# ATMega8Motherboard.net
KiCad netlist of a schematic drawn in EAGLE
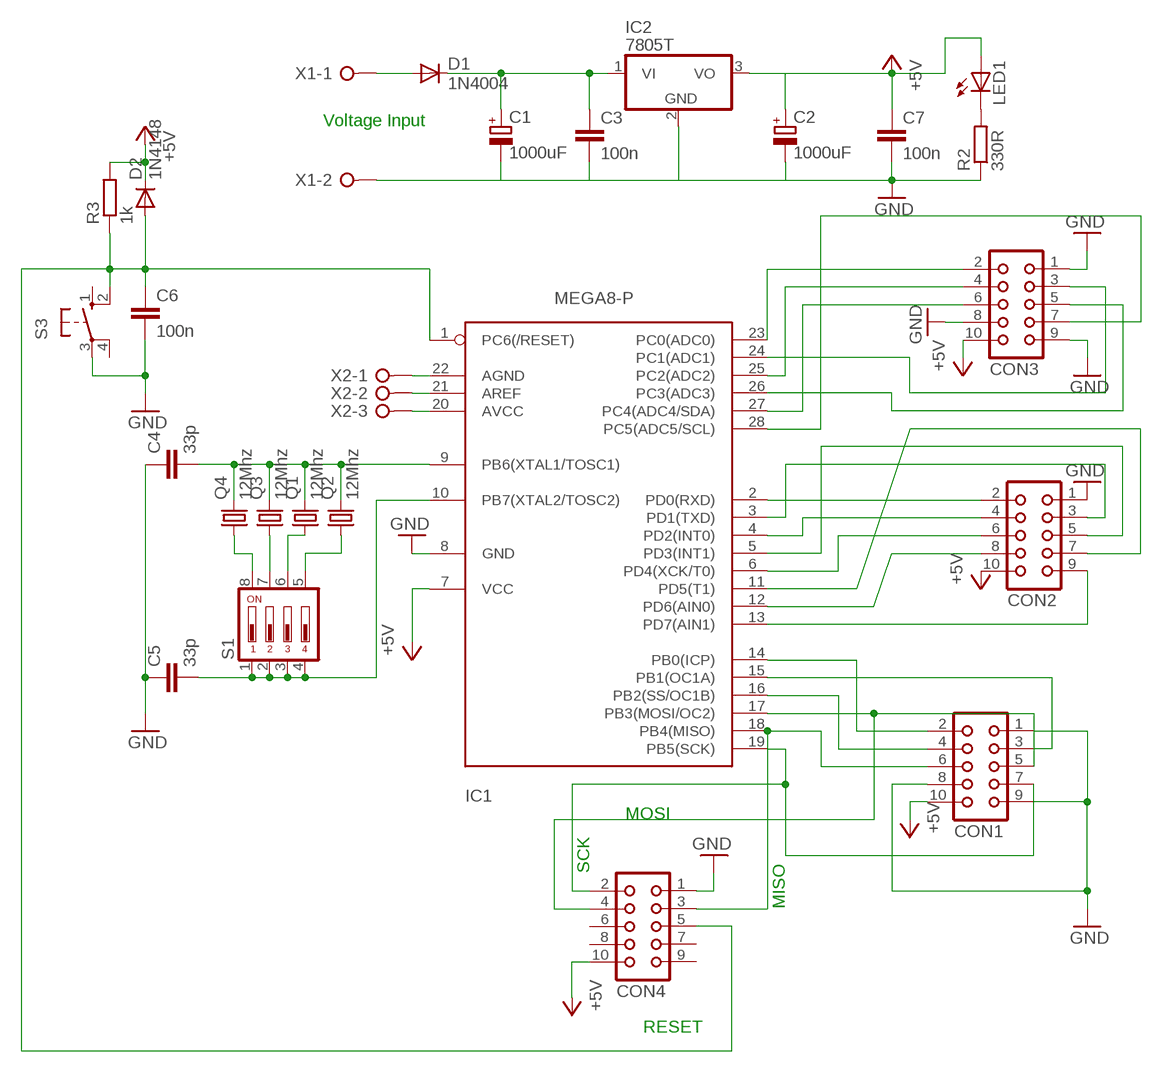
[diagram p0: schematic, sheet 1]

(export (version "E")
  (design (tool "Eeschema 10.0.6"))
  (components
    (comp (ref "C1")
      (value "1000uF")
      (footprint "eagle-import:E2,5-7")
      (libsource (lib "eagle-import") (part "CPOL-EUE2.5-7"))
    )
    (comp (ref "C2")
      (value "1000uF")
      (footprint "eagle-import:E2,5-7")
      (libsource (lib "eagle-import") (part "CPOL-EUE2.5-7"))
    )
    (comp (ref "C3")
      (value "100n")
      (footprint "eagle-import:C025-024X044")
      (libsource (lib "eagle-import") (part "C-EU025-024X044"))
    )
    (comp (ref "C4")
      (value "33p")
      (footprint "eagle-import:C025-024X044")
      (libsource (lib "eagle-import") (part "C-EU025-024X044"))
    )
    (comp (ref "C5")
      (value "33p")
      (footprint "eagle-import:C025-024X044")
      (libsource (lib "eagle-import") (part "C-EU025-024X044"))
    )
    (comp (ref "C6")
      (value "100n")
      (footprint "eagle-import:C025-024X044")
      (libsource (lib "eagle-import") (part "C-EU025-024X044"))
    )
    (comp (ref "C7")
      (value "100n")
      (footprint "eagle-import:C025-024X044")
      (libsource (lib "eagle-import") (part "C-EU025-024X044"))
    )
    (comp (ref "CON1")
      (value "CON10")
      (footprint "eagle-import:CON10")
      (libsource (lib "eagle-import") (part "CON10"))
    )
    (comp (ref "CON2")
      (value "CON10")
      (footprint "eagle-import:CON10")
      (libsource (lib "eagle-import") (part "CON10"))
    )
    (comp (ref "CON3")
      (value "CON10")
      (footprint "eagle-import:CON10")
      (libsource (lib "eagle-import") (part "CON10"))
    )
    (comp (ref "CON4")
      (value "CON10")
      (footprint "eagle-import:CON10")
      (libsource (lib "eagle-import") (part "CON10"))
    )
    (comp (ref "D1")
      (value "1N4004")
      (footprint "eagle-import:DO41-10")
      (libsource (lib "eagle-import") (part "1N4004"))
    )
    (comp (ref "D2")
      (value "1N4148")
      (footprint "eagle-import:DO35-10")
      (libsource (lib "eagle-import") (part "1N4148"))
    )
    (comp (ref "IC1")
      (value "MEGA8-P")
      (footprint "eagle-import:DIL28-3")
      (libsource (lib "eagle-import") (part "MEGA8-P"))
    )
    (comp (ref "IC2")
      (value "7805T")
      (footprint "eagle-import:TO220H")
      (libsource (lib "eagle-import") (part "78T05"))
    )
    (comp (ref "LED1")
      (value "LED5MM")
      (footprint "eagle-import:LED5MM")
      (libsource (lib "eagle-import") (part "LED5MM"))
    )
    (comp (ref "Q1")
      (value "12Mhz")
      (footprint "eagle-import:HC18U-V")
      (libsource (lib "eagle-import") (part "CRYSTALHC18U-V"))
    )
    (comp (ref "Q2")
      (value "12Mhz")
      (footprint "eagle-import:HC18U-V")
      (libsource (lib "eagle-import") (part "CRYSTALHC18U-V"))
    )
    (comp (ref "Q3")
      (value "12Mhz")
      (footprint "eagle-import:HC18U-V")
      (libsource (lib "eagle-import") (part "CRYSTALHC18U-V"))
    )
    (comp (ref "Q4")
      (value "12Mhz")
      (footprint "eagle-import:HC18U-V")
      (libsource (lib "eagle-import") (part "CRYSTALHC18U-V"))
    )
    (comp (ref "R2")
      (value "330R")
      (footprint "eagle-import:0204_5")
      (libsource (lib "eagle-import") (part "R-EU_0204/5"))
    )
    (comp (ref "R3")
      (value "1k")
      (footprint "eagle-import:0204_5")
      (libsource (lib "eagle-import") (part "R-EU_0204/5"))
    )
    (comp (ref "S1")
      (value "DIP04YL")
      (footprint "eagle-import:DIP04YL")
      (libsource (lib "eagle-import") (part "DIP04YL"))
    )
    (comp (ref "S3")
      (value "10-XX")
      (footprint "eagle-import:B3F-10XX")
      (fields (field (name "MPN") "B3F-1000"))
      (libsource (lib "eagle-import") (part "10-XX"))
    )
    (comp (ref "X1")
      (value "W237-02P")
      (footprint "eagle-import:W237-132")
      (libsource (lib "eagle-import") (part "W237-02P"))
    )
    (comp (ref "X2")
      (value "W237-03P")
      (footprint "eagle-import:W237-133")
      (libsource (lib "eagle-import") (part "W237-03P"))
    )
  )
  (nets
    (net (code "1") (name "+5V") (class "Default")
      (node (ref "C2") (pin "+") (pinfunction "+_+") (pintype "passive"))
      (node (ref "C7") (pin "1") (pinfunction "1_1") (pintype "passive"))
      (node (ref "CON1") (pin "10") (pinfunction "10_10") (pintype "passive"))
      (node (ref "CON2") (pin "10") (pinfunction "10_10") (pintype "passive"))
      (node (ref "CON3") (pin "10") (pinfunction "10_10") (pintype "passive"))
      (node (ref "CON4") (pin "10") (pinfunction "10_10") (pintype "passive"))
      (node (ref "D2") (pin "C") (pinfunction "C_C") (pintype "passive"))
      (node (ref "IC1") (pin "7") (pinfunction "VCC_7") (pintype "bidirectional"))
      (node (ref "IC2") (pin "3") (pinfunction "VO_3") (pintype "passive"))
      (node (ref "LED1") (pin "A") (pinfunction "A_A") (pintype "passive"))
      (node (ref "R3") (pin "2") (pinfunction "2_2") (pintype "passive"))
    )
    (net (code "2") (name "GND") (class "Default")
      (node (ref "C1") (pin "-") (pinfunction "-_-") (pintype "passive"))
      (node (ref "C2") (pin "-") (pinfunction "-_-") (pintype "passive"))
      (node (ref "C3") (pin "2") (pinfunction "2_2") (pintype "passive"))
      (node (ref "C4") (pin "1") (pinfunction "1_1") (pintype "passive"))
      (node (ref "C5") (pin "1") (pinfunction "1_1") (pintype "passive"))
      (node (ref "C6") (pin "2") (pinfunction "2_2") (pintype "passive"))
      (node (ref "C7") (pin "2") (pinfunction "2_2") (pintype "passive"))
      (node (ref "CON1") (pin "1") (pinfunction "1_1") (pintype "passive"))
      (node (ref "CON1") (pin "8") (pinfunction "8_8") (pintype "passive"))
      (node (ref "CON1") (pin "9") (pinfunction "9_9") (pintype "passive"))
      (node (ref "CON2") (pin "1") (pinfunction "1_1") (pintype "passive"))
      (node (ref "CON3") (pin "1") (pinfunction "1_1") (pintype "passive"))
      (node (ref "CON3") (pin "8") (pinfunction "8_8") (pintype "passive"))
      (node (ref "CON3") (pin "9") (pinfunction "9_9") (pintype "passive"))
      (node (ref "CON4") (pin "1") (pinfunction "1_1") (pintype "passive"))
      (node (ref "IC1") (pin "8") (pinfunction "GND_8") (pintype "bidirectional"))
      (node (ref "IC2") (pin "2") (pinfunction "GND_2") (pintype "passive"))
      (node (ref "R2") (pin "1") (pinfunction "1_1") (pintype "passive"))
      (node (ref "S3") (pin "3") (pinfunction "P_3") (pintype "passive"))
      (node (ref "X1") (pin "2") (pinfunction "KL_2") (pintype "passive"))
    )
    (net (code "3") (name "Net-(IC1-AGND)") (class "Default")
      (node (ref "IC1") (pin "22") (pinfunction "AGND_22") (pintype "bidirectional"))
      (node (ref "X2") (pin "1") (pinfunction "KL_1") (pintype "passive"))
    )
    (net (code "4") (name "Net-(IC1-AREF)") (class "Default")
      (node (ref "IC1") (pin "21") (pinfunction "AREF_21") (pintype "bidirectional"))
      (node (ref "X2") (pin "2") (pinfunction "KL_2") (pintype "passive"))
    )
    (net (code "5") (name "Net-(IC1-AVCC)") (class "Default")
      (node (ref "IC1") (pin "20") (pinfunction "AVCC_20") (pintype "bidirectional"))
      (node (ref "X2") (pin "3") (pinfunction "KL_3") (pintype "passive"))
    )
    (net (code "6") (name "Net-(IC1-PB0(ICP))") (class "Default")
      (node (ref "CON1") (pin "2") (pinfunction "2_2") (pintype "passive"))
      (node (ref "IC1") (pin "14") (pinfunction "PB0(ICP)_14") (pintype "bidirectional"))
    )
    (net (code "7") (name "Net-(IC1-PB1(OC1A))") (class "Default")
      (node (ref "CON1") (pin "3") (pinfunction "3_3") (pintype "passive"))
      (node (ref "IC1") (pin "15") (pinfunction "PB1(OC1A)_15") (pintype "bidirectional"))
    )
    (net (code "8") (name "Net-(IC1-PB2(SS{slash}OC1B))") (class "Default")
      (node (ref "CON1") (pin "4") (pinfunction "4_4") (pintype "passive"))
      (node (ref "IC1") (pin "16") (pinfunction "PB2(SS/OC1B)_16") (pintype "bidirectional"))
    )
    (net (code "9") (name "Net-(IC1-PB3(MOSI{slash}OC2))") (class "Default")
      (node (ref "CON1") (pin "5") (pinfunction "5_5") (pintype "passive"))
      (node (ref "CON4") (pin "4") (pinfunction "4_4") (pintype "passive"))
      (node (ref "IC1") (pin "17") (pinfunction "PB3(MOSI/OC2)_17") (pintype "bidirectional"))
    )
    (net (code "10") (name "Net-(IC1-PB4(MISO))") (class "Default")
      (node (ref "CON1") (pin "6") (pinfunction "6_6") (pintype "passive"))
      (node (ref "CON4") (pin "3") (pinfunction "3_3") (pintype "passive"))
      (node (ref "IC1") (pin "18") (pinfunction "PB4(MISO)_18") (pintype "bidirectional"))
    )
    (net (code "11") (name "Net-(IC1-PB5(SCK))") (class "Default")
      (node (ref "CON1") (pin "7") (pinfunction "7_7") (pintype "passive"))
      (node (ref "CON4") (pin "2") (pinfunction "2_2") (pintype "passive"))
      (node (ref "IC1") (pin "19") (pinfunction "PB5(SCK)_19") (pintype "bidirectional"))
    )
    (net (code "12") (name "Net-(IC1-PB6(XTAL1{slash}TOSC1))") (class "Default")
      (node (ref "C4") (pin "2") (pinfunction "2_2") (pintype "passive"))
      (node (ref "IC1") (pin "9") (pinfunction "PB6(XTAL1/TOSC1)_9") (pintype "bidirectional"))
      (node (ref "Q1") (pin "2") (pinfunction "2_2") (pintype "passive"))
      (node (ref "Q2") (pin "2") (pinfunction "2_2") (pintype "passive"))
      (node (ref "Q3") (pin "2") (pinfunction "2_2") (pintype "passive"))
      (node (ref "Q4") (pin "2") (pinfunction "2_2") (pintype "passive"))
    )
    (net (code "13") (name "Net-(IC1-PB7(XTAL2{slash}TOSC2))") (class "Default")
      (node (ref "C5") (pin "2") (pinfunction "2_2") (pintype "passive"))
      (node (ref "IC1") (pin "10") (pinfunction "PB7(XTAL2/TOSC2)_10") (pintype "bidirectional"))
      (node (ref "S1") (pin "1") (pinfunction "1_1") (pintype "passive"))
      (node (ref "S1") (pin "2") (pinfunction "2_2") (pintype "passive"))
      (node (ref "S1") (pin "3") (pinfunction "3_3") (pintype "passive"))
      (node (ref "S1") (pin "4") (pinfunction "4_4") (pintype "passive"))
    )
    (net (code "14") (name "Net-(IC1-PC0(ADC0))") (class "Default")
      (node (ref "CON3") (pin "2") (pinfunction "2_2") (pintype "passive"))
      (node (ref "IC1") (pin "23") (pinfunction "PC0(ADC0)_23") (pintype "bidirectional"))
    )
    (net (code "15") (name "Net-(IC1-PC1(ADC1))") (class "Default")
      (node (ref "CON3") (pin "3") (pinfunction "3_3") (pintype "passive"))
      (node (ref "IC1") (pin "24") (pinfunction "PC1(ADC1)_24") (pintype "bidirectional"))
    )
    (net (code "16") (name "Net-(IC1-PC2(ADC2))") (class "Default")
      (node (ref "CON3") (pin "4") (pinfunction "4_4") (pintype "passive"))
      (node (ref "IC1") (pin "25") (pinfunction "PC2(ADC2)_25") (pintype "bidirectional"))
    )
    (net (code "17") (name "Net-(IC1-PC3(ADC3))") (class "Default")
      (node (ref "CON3") (pin "5") (pinfunction "5_5") (pintype "passive"))
      (node (ref "IC1") (pin "26") (pinfunction "PC3(ADC3)_26") (pintype "bidirectional"))
    )
    (net (code "18") (name "Net-(IC1-PC4(ADC4{slash}SDA))") (class "Default")
      (node (ref "CON3") (pin "6") (pinfunction "6_6") (pintype "passive"))
      (node (ref "IC1") (pin "27") (pinfunction "PC4(ADC4/SDA)_27") (pintype "bidirectional"))
    )
    (net (code "19") (name "Net-(IC1-PC5(ADC5{slash}SCL))") (class "Default")
      (node (ref "CON3") (pin "7") (pinfunction "7_7") (pintype "passive"))
      (node (ref "IC1") (pin "28") (pinfunction "PC5(ADC5/SCL)_28") (pintype "bidirectional"))
    )
    (net (code "20") (name "Net-(IC1-PC6({slash}RESET))") (class "Default")
      (node (ref "C6") (pin "1") (pinfunction "1_1") (pintype "passive"))
      (node (ref "CON4") (pin "5") (pinfunction "5_5") (pintype "passive"))
      (node (ref "D2") (pin "A") (pinfunction "A_A") (pintype "passive"))
      (node (ref "IC1") (pin "1") (pinfunction "PC6(/RESET)_1") (pintype "bidirectional"))
      (node (ref "R3") (pin "1") (pinfunction "1_1") (pintype "passive"))
      (node (ref "S3") (pin "2") (pinfunction "S1_2") (pintype "passive"))
    )
    (net (code "21") (name "Net-(IC1-PD0(RXD))") (class "Default")
      (node (ref "CON2") (pin "2") (pinfunction "2_2") (pintype "passive"))
      (node (ref "IC1") (pin "2") (pinfunction "PD0(RXD)_2") (pintype "bidirectional"))
    )
    (net (code "22") (name "Net-(IC1-PD1(TXD))") (class "Default")
      (node (ref "CON2") (pin "3") (pinfunction "3_3") (pintype "passive"))
      (node (ref "IC1") (pin "3") (pinfunction "PD1(TXD)_3") (pintype "bidirectional"))
    )
    (net (code "23") (name "Net-(IC1-PD2(INT0))") (class "Default")
      (node (ref "CON2") (pin "4") (pinfunction "4_4") (pintype "passive"))
      (node (ref "IC1") (pin "4") (pinfunction "PD2(INT0)_4") (pintype "bidirectional"))
    )
    (net (code "24") (name "Net-(IC1-PD3(INT1))") (class "Default")
      (node (ref "CON2") (pin "5") (pinfunction "5_5") (pintype "passive"))
      (node (ref "IC1") (pin "5") (pinfunction "PD3(INT1)_5") (pintype "bidirectional"))
    )
    (net (code "25") (name "Net-(IC1-PD4(XCK{slash}T0))") (class "Default")
      (node (ref "CON2") (pin "6") (pinfunction "6_6") (pintype "passive"))
      (node (ref "IC1") (pin "6") (pinfunction "PD4(XCK/T0)_6") (pintype "bidirectional"))
    )
    (net (code "26") (name "Net-(IC1-PD5(T1))") (class "Default")
      (node (ref "CON2") (pin "7") (pinfunction "7_7") (pintype "passive"))
      (node (ref "IC1") (pin "11") (pinfunction "PD5(T1)_11") (pintype "bidirectional"))
    )
    (net (code "27") (name "Net-(IC1-PD6(AIN0))") (class "Default")
      (node (ref "CON2") (pin "8") (pinfunction "8_8") (pintype "passive"))
      (node (ref "IC1") (pin "12") (pinfunction "PD6(AIN0)_12") (pintype "bidirectional"))
    )
    (net (code "28") (name "Net-(IC1-PD7(AIN1))") (class "Default")
      (node (ref "CON2") (pin "9") (pinfunction "9_9") (pintype "passive"))
      (node (ref "IC1") (pin "13") (pinfunction "PD7(AIN1)_13") (pintype "bidirectional"))
    )
    (net (code "29") (name "Net-(IC2-VI)") (class "Default")
      (node (ref "C1") (pin "+") (pinfunction "+_+") (pintype "passive"))
      (node (ref "C3") (pin "1") (pinfunction "1_1") (pintype "passive"))
      (node (ref "D1") (pin "C") (pinfunction "C_C") (pintype "passive"))
      (node (ref "IC2") (pin "1") (pinfunction "VI_1") (pintype "input"))
    )
    (net (code "30") (name "Net-(LED1-C)") (class "Default")
      (node (ref "LED1") (pin "K") (pinfunction "C_K") (pintype "passive"))
      (node (ref "R2") (pin "2") (pinfunction "2_2") (pintype "passive"))
    )
    (net (code "31") (name "Net-(Q1-Pad1)") (class "Default")
      (node (ref "Q1") (pin "1") (pinfunction "1_1") (pintype "passive"))
      (node (ref "S1") (pin "6") (pinfunction "6_6") (pintype "passive"))
    )
    (net (code "32") (name "Net-(Q2-Pad1)") (class "Default")
      (node (ref "Q2") (pin "1") (pinfunction "1_1") (pintype "passive"))
      (node (ref "S1") (pin "5") (pinfunction "5_5") (pintype "passive"))
    )
    (net (code "33") (name "Net-(Q3-Pad1)") (class "Default")
      (node (ref "Q3") (pin "1") (pinfunction "1_1") (pintype "passive"))
      (node (ref "S1") (pin "7") (pinfunction "7_7") (pintype "passive"))
    )
    (net (code "34") (name "Net-(Q4-Pad1)") (class "Default")
      (node (ref "Q4") (pin "1") (pinfunction "1_1") (pintype "passive"))
      (node (ref "S1") (pin "8") (pinfunction "8_8") (pintype "passive"))
    )
    (net (code "35") (name "Net-(X1A-KL)") (class "Default")
      (node (ref "D1") (pin "A") (pinfunction "A_A") (pintype "passive"))
      (node (ref "X1") (pin "1") (pinfunction "KL_1") (pintype "passive"))
    )
    (net (code "36") (name "unconnected-(CON4-Pad6)") (class "Default")
      (node (ref "CON4") (pin "6") (pinfunction "6_6") (pintype "passive"))
    )
    (net (code "37") (name "unconnected-(CON4-Pad7)") (class "Default")
      (node (ref "CON4") (pin "7") (pinfunction "7_7") (pintype "passive"))
    )
    (net (code "38") (name "unconnected-(CON4-Pad8)") (class "Default")
      (node (ref "CON4") (pin "8") (pinfunction "8_8") (pintype "passive"))
    )
    (net (code "39") (name "unconnected-(CON4-Pad9)") (class "Default")
      (node (ref "CON4") (pin "9") (pinfunction "9_9") (pintype "passive"))
    )
    (net (code "40") (name "unconnected-(S3-P1-Pad4)") (class "Default")
      (node (ref "S3") (pin "4") (pinfunction "P1_4") (pintype "passive"))
    )
    (net (code "41") (name "unconnected-(S3-S-Pad1)") (class "Default")
      (node (ref "S3") (pin "1") (pinfunction "S_1") (pintype "passive"))
    )
  )
)
